# 102711.net
KiCad netlist of a schematic drawn in Altium Designer
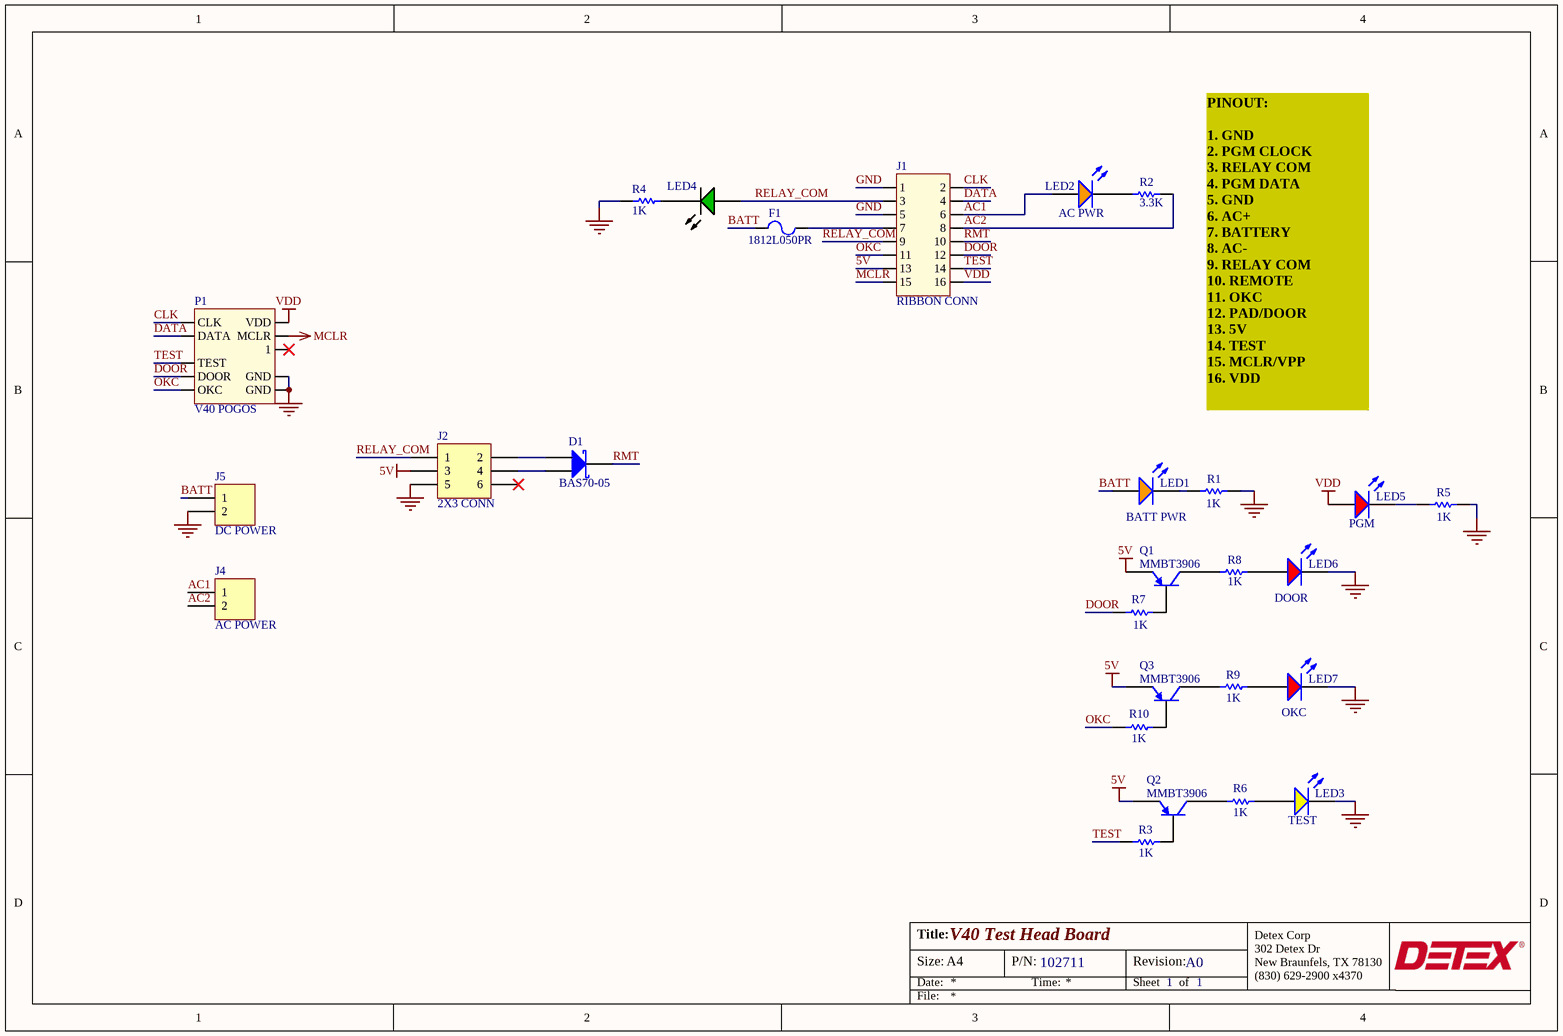
[diagram p0: 102711.SchDoc]

(export (version "E")
  (design (tool "Eeschema 10.0.6"))
  (components
    (comp (ref "D1")
      (value "BAS70-05")
      (footprint "SOT-23_M")
      (description "Dual Schottky Diode")
      (fields (field (name "MFR") "DIODES, INC"))
      (libsource (lib "Miscellaneous Devices") (part "D Schottky"))
    )
    (comp (ref "F1")
      (value "1812L050PR")
      (footprint "LFUS-1812L050_V")
      (fields (field (name "TOLERANCE") "1%"))
      (libsource (lib "Altium Content Vault") (part "CMP-1700-00002-1"))
    )
    (comp (ref "J1")
      (value "2x8 Header")
      (footprint "HDR2X8")
      (fields (field (name "DESC") "RIBBON CONN"))
      (libsource (lib "102709") (part "2x9 Header"))
    )
    (comp (ref "J2")
      (value "2X3 CONN")
      (footprint "HDR2X3")
      (description "Header, 3-Pin, Dual row")
      (fields (field (name "PUBLISHER") "Altium Limited"))
      (libsource (lib "Miscellaneous Connectors") (part "Header 3X2"))
    )
    (comp (ref "J4")
      (value "AC POWER")
      (footprint "HDR1X2")
      (description "Header, 2-Pin")
      (fields (field (name "PUBLISHER") "Altium Limited"))
      (libsource (lib "Miscellaneous Connectors") (part "Header 2"))
    )
    (comp (ref "J5")
      (value "DC POWER")
      (footprint "BAT_CONN")
      (description "Header, 2-Pin")
      (fields (field (name "PUBLISHER") "Altium Limited"))
      (libsource (lib "Miscellaneous Connectors") (part "Header 2"))
    )
    (comp (ref "LED1")
      (value "BATT PWR")
      (footprint "LTST-C170YKT_V")
      (libsource (lib "altium-import") (part "root_0_SYM-0251-00006-1_"))
    )
    (comp (ref "LED2")
      (value "AC PWR")
      (footprint "LTST-C170YKT_V")
      (libsource (lib "altium-import") (part "root_0_SYM-0251-00006-1_"))
    )
    (comp (ref "LED3")
      (value "LTST-C170YKT")
      (footprint "LTST-C170YKT_V")
      (description "LED Uni-Color Yellow, 60 mW, 80 mA, -55 to 85 degC, 2-Pin SMD, RoHS, Tape and Reel")
      (fields (field (name "MANUFACTURER") "Lite-On") (field (name "DESC") "TEST"))
      (libsource (lib "altium-import") (part "root_0_CMP-1674-00003-5_"))
    )
    (comp (ref "LED4")
      (value "LTST-C190GKT")
      (footprint "LTST-C170YKT_V")
      (description "LED Uni-Color Green, 100 mW, 5 V, -55 to 85 degC, 2-Pin SMD, RoHS, Tape and Reel")
      (libsource (lib "altium-import") (part "root_2_CMP-1674-00007-1_"))
    )
    (comp (ref "LED5")
      (value "LTST-C170CKT")
      (footprint "LTST-C170YKT_V")
      (description "LED Uni-Color Red, 100 mW, 200 mA, -55 to 85 degC, 2-Pin SMD, RoHS, Tape and Reel")
      (fields (field (name "MANUFACTURER") "Lite-On") (field (name "DESC") "PGM"))
      (libsource (lib "altium-import") (part "root_0_CMP-1674-00001-5_"))
    )
    (comp (ref "LED6")
      (value "LTST-C170CKT")
      (footprint "LTST-C170YKT_V")
      (description "LED Uni-Color Red, 100 mW, 200 mA, -55 to 85 degC, 2-Pin SMD, RoHS, Tape and Reel")
      (fields (field (name "MANUFACTURER") "Lite-On") (field (name "DESC") "DOOR"))
      (libsource (lib "altium-import") (part "root_0_CMP-1674-00001-5_"))
    )
    (comp (ref "LED7")
      (value "LTST-C170CKT")
      (footprint "LTST-C170YKT_V")
      (description "LED Uni-Color Red, 100 mW, 200 mA, -55 to 85 degC, 2-Pin SMD, RoHS, Tape and Reel")
      (fields (field (name "MANUFACTURER") "Lite-On") (field (name "DESC") "OKC"))
      (libsource (lib "altium-import") (part "root_0_CMP-1674-00001-5_"))
    )
    (comp (ref "P1")
      (value "V40 POGOS")
      (footprint "V40_POGOS")
      (libsource (lib "102711") (part "V40_POGOS"))
    )
    (comp (ref "Q1")
      (value "MMBT3906")
      (footprint "FAIR-SOT23-3_V")
      (description "PNP General-Purpose Amplifier, 40 V, 0.2 A, -55 to 150 degC, 3-Pin SOT23, RoHS, Tape and Reel")
      (fields (field (name "TOLERANCE") "20%"))
      (libsource (lib "Altium Content Vault") (part "CMP-1670-00011-1"))
    )
    (comp (ref "Q2")
      (value "MMBT3906")
      (footprint "FAIR-SOT23-3_V")
      (description "PNP General-Purpose Amplifier, 40 V, 0.2 A, -55 to 150 degC, 3-Pin SOT23, RoHS, Tape and Reel")
      (fields (field (name "TOLERANCE") "20%"))
      (libsource (lib "Altium Content Vault") (part "CMP-1670-00011-1"))
    )
    (comp (ref "Q3")
      (value "MMBT3906")
      (footprint "FAIR-SOT23-3_V")
      (description "PNP General-Purpose Amplifier, 40 V, 0.2 A, -55 to 150 degC, 3-Pin SOT23, RoHS, Tape and Reel")
      (fields (field (name "TOLERANCE") "20%"))
      (libsource (lib "Altium Content Vault") (part "CMP-1670-00011-1"))
    )
    (comp (ref "R1")
      (value "1K")
      (footprint "RESC0805(2012)_M")
      (description "Resistor")
      (fields (field (name "Comment") "Res1") (field (name "PUBLISHER") "Altium Limited"))
      (libsource (lib "Miscellaneous Devices") (part "Res1"))
    )
    (comp (ref "R2")
      (value "3.3K")
      (footprint "RESC0805(2012)_M")
      (description "Resistor")
      (fields (field (name "Comment") "Res1") (field (name "PUBLISHER") "Altium Limited"))
      (libsource (lib "Miscellaneous Devices") (part "Res1"))
    )
    (comp (ref "R3")
      (value "1K")
      (footprint "RESC0805(2012)_M")
      (description "Resistor")
      (fields (field (name "Comment") "Res1") (field (name "PUBLISHER") "Altium Limited"))
      (libsource (lib "Miscellaneous Devices") (part "Res1"))
    )
    (comp (ref "R4")
      (value "1K")
      (footprint "RESC0805(2012)_M")
      (description "Resistor")
      (fields (field (name "Comment") "Res1") (field (name "PUBLISHER") "Altium Limited"))
      (libsource (lib "Miscellaneous Devices") (part "Res1"))
    )
    (comp (ref "R5")
      (value "1K")
      (footprint "RESC0805(2012)_M")
      (description "Resistor")
      (fields (field (name "Comment") "Res1") (field (name "PUBLISHER") "Altium Limited"))
      (libsource (lib "Miscellaneous Devices") (part "Res1"))
    )
    (comp (ref "R6")
      (value "1K")
      (footprint "RESC0805(2012)_M")
      (description "Resistor")
      (fields (field (name "Comment") "Res1") (field (name "PUBLISHER") "Altium Limited"))
      (libsource (lib "Miscellaneous Devices") (part "Res1"))
    )
    (comp (ref "R7")
      (value "1K")
      (footprint "RESC0805(2012)_M")
      (description "Resistor")
      (fields (field (name "Comment") "Res1") (field (name "PUBLISHER") "Altium Limited"))
      (libsource (lib "Miscellaneous Devices") (part "Res1"))
    )
    (comp (ref "R8")
      (value "1K")
      (footprint "RESC0805(2012)_M")
      (description "Resistor")
      (fields (field (name "Comment") "Res1") (field (name "PUBLISHER") "Altium Limited"))
      (libsource (lib "Miscellaneous Devices") (part "Res1"))
    )
    (comp (ref "R9")
      (value "1K")
      (footprint "RESC0805(2012)_M")
      (description "Resistor")
      (fields (field (name "Comment") "Res1") (field (name "PUBLISHER") "Altium Limited"))
      (libsource (lib "Miscellaneous Devices") (part "Res1"))
    )
    (comp (ref "R10")
      (value "1K")
      (footprint "RESC0805(2012)_M")
      (description "Resistor")
      (fields (field (name "Comment") "Res1") (field (name "PUBLISHER") "Altium Limited"))
      (libsource (lib "Miscellaneous Devices") (part "Res1"))
    )
  )
  (nets
    (net (code "1") (name "/AC1") (class "Default")
      (node (ref "J1") (pin "6") (pinfunction "6_6") (pintype "passive"))
      (node (ref "J4") (pin "1") (pinfunction "1_1") (pintype "passive"))
      (node (ref "LED2") (pin "1") (pinfunction "A_1") (pintype "passive"))
    )
    (net (code "2") (name "/AC2") (class "Default")
      (node (ref "J1") (pin "8") (pinfunction "8_8") (pintype "passive"))
      (node (ref "J4") (pin "2") (pinfunction "2_2") (pintype "passive"))
      (node (ref "R2") (pin "2") (pinfunction "2_2") (pintype "passive"))
    )
    (net (code "3") (name "/BATT") (class "Default")
      (node (ref "F1") (pin "1") (pinfunction "1_1") (pintype "passive"))
      (node (ref "J5") (pin "1") (pinfunction "1_1") (pintype "passive"))
      (node (ref "LED1") (pin "1") (pinfunction "A_1") (pintype "passive"))
    )
    (net (code "4") (name "/CLK") (class "Default")
      (node (ref "J1") (pin "2") (pinfunction "2_2") (pintype "passive"))
      (node (ref "P1") (pin "3") (pinfunction "CLK_3") (pintype "passive"))
    )
    (net (code "5") (name "/DATA") (class "Default")
      (node (ref "J1") (pin "4") (pinfunction "4_4") (pintype "passive"))
      (node (ref "P1") (pin "4") (pinfunction "DATA_4") (pintype "passive"))
    )
    (net (code "6") (name "/DOOR") (class "Default")
      (node (ref "J1") (pin "12") (pinfunction "12_12") (pintype "passive"))
      (node (ref "P1") (pin "9") (pinfunction "DOOR_9") (pintype "passive"))
      (node (ref "R7") (pin "1") (pinfunction "1_1") (pintype "passive"))
    )
    (net (code "7") (name "/OKC") (class "Default")
      (node (ref "J1") (pin "11") (pinfunction "11_11") (pintype "passive"))
      (node (ref "P1") (pin "10") (pinfunction "OKC_10") (pintype "passive"))
      (node (ref "R10") (pin "1") (pinfunction "1_1") (pintype "passive"))
    )
    (net (code "8") (name "/RELAY_COM") (class "Default")
      (node (ref "J1") (pin "3") (pinfunction "3_3") (pintype "passive"))
      (node (ref "J1") (pin "9") (pinfunction "9_9") (pintype "passive"))
      (node (ref "J2") (pin "1") (pinfunction "1_1") (pintype "passive"))
      (node (ref "LED4") (pin "1") (pinfunction "A_1") (pintype "passive"))
    )
    (net (code "9") (name "/RMT") (class "Default")
      (node (ref "D1") (pin "3") (pinfunction "K_3") (pintype "passive"))
      (node (ref "J1") (pin "10") (pinfunction "10_10") (pintype "passive"))
    )
    (net (code "10") (name "/TEST") (class "Default")
      (node (ref "J1") (pin "14") (pinfunction "14_14") (pintype "passive"))
      (node (ref "P1") (pin "7") (pinfunction "TEST_7") (pintype "passive"))
      (node (ref "R3") (pin "1") (pinfunction "1_1") (pintype "passive"))
    )
    (net (code "11") (name "5V") (class "Default")
      (node (ref "J1") (pin "13") (pinfunction "13_13") (pintype "passive"))
      (node (ref "J2") (pin "3") (pinfunction "3_3") (pintype "passive"))
      (node (ref "Q1") (pin "2") (pinfunction "E_2") (pintype "passive"))
      (node (ref "Q2") (pin "2") (pinfunction "E_2") (pintype "passive"))
      (node (ref "Q3") (pin "2") (pinfunction "E_2") (pintype "passive"))
    )
    (net (code "12") (name "GND") (class "Default")
      (node (ref "J1") (pin "1") (pinfunction "1_1") (pintype "passive"))
      (node (ref "J1") (pin "5") (pinfunction "5_5") (pintype "passive"))
      (node (ref "J2") (pin "5") (pinfunction "5_5") (pintype "passive"))
      (node (ref "J5") (pin "2") (pinfunction "2_2") (pintype "passive"))
      (node (ref "LED3") (pin "2") (pinfunction "K_2") (pintype "passive"))
      (node (ref "LED6") (pin "2") (pinfunction "K_2") (pintype "passive"))
      (node (ref "LED7") (pin "2") (pinfunction "K_2") (pintype "passive"))
      (node (ref "P1") (pin "2") (pinfunction "GND_2") (pintype "passive"))
      (node (ref "P1") (pin "8") (pinfunction "GND_8") (pintype "passive"))
      (node (ref "R1") (pin "2") (pinfunction "2_2") (pintype "passive"))
      (node (ref "R4") (pin "2") (pinfunction "2_2") (pintype "passive"))
      (node (ref "R5") (pin "2") (pinfunction "2_2") (pintype "passive"))
    )
    (net (code "13") (name "MCLR") (class "Default")
      (node (ref "J1") (pin "15") (pinfunction "15_15") (pintype "passive"))
      (node (ref "P1") (pin "5") (pinfunction "MCLR_5") (pintype "passive"))
    )
    (net (code "14") (name "Net-(D1-A-Pad1)") (class "Default")
      (node (ref "D1") (pin "1") (pinfunction "A_1") (pintype "passive"))
      (node (ref "J2") (pin "4") (pinfunction "4_4") (pintype "passive"))
    )
    (net (code "15") (name "Net-(D1-A-Pad2)") (class "Default")
      (node (ref "D1") (pin "2") (pinfunction "A_2") (pintype "passive"))
      (node (ref "J2") (pin "2") (pinfunction "2_2") (pintype "passive"))
    )
    (net (code "16") (name "Net-(F1-Pad2)") (class "Default")
      (node (ref "F1") (pin "2") (pinfunction "2_2") (pintype "passive"))
      (node (ref "J1") (pin "7") (pinfunction "7_7") (pintype "passive"))
    )
    (net (code "17") (name "Net-(LED1-K)") (class "Default")
      (node (ref "LED1") (pin "2") (pinfunction "K_2") (pintype "passive"))
      (node (ref "R1") (pin "1") (pinfunction "1_1") (pintype "passive"))
    )
    (net (code "18") (name "Net-(LED2-K)") (class "Default")
      (node (ref "LED2") (pin "2") (pinfunction "K_2") (pintype "passive"))
      (node (ref "R2") (pin "1") (pinfunction "1_1") (pintype "passive"))
    )
    (net (code "19") (name "Net-(LED3-A)") (class "Default")
      (node (ref "LED3") (pin "1") (pinfunction "A_1") (pintype "passive"))
      (node (ref "R6") (pin "2") (pinfunction "2_2") (pintype "passive"))
    )
    (net (code "20") (name "Net-(LED4-K)") (class "Default")
      (node (ref "LED4") (pin "2") (pinfunction "K_2") (pintype "passive"))
      (node (ref "R4") (pin "1") (pinfunction "1_1") (pintype "passive"))
    )
    (net (code "21") (name "Net-(LED5-K)") (class "Default")
      (node (ref "LED5") (pin "2") (pinfunction "K_2") (pintype "passive"))
      (node (ref "R5") (pin "1") (pinfunction "1_1") (pintype "passive"))
    )
    (net (code "22") (name "Net-(LED6-A)") (class "Default")
      (node (ref "LED6") (pin "1") (pinfunction "A_1") (pintype "passive"))
      (node (ref "R8") (pin "2") (pinfunction "2_2") (pintype "passive"))
    )
    (net (code "23") (name "Net-(LED7-A)") (class "Default")
      (node (ref "LED7") (pin "1") (pinfunction "A_1") (pintype "passive"))
      (node (ref "R9") (pin "2") (pinfunction "2_2") (pintype "passive"))
    )
    (net (code "24") (name "Net-(Q1-B)") (class "Default")
      (node (ref "Q1") (pin "1") (pinfunction "B_1") (pintype "passive"))
      (node (ref "R7") (pin "2") (pinfunction "2_2") (pintype "passive"))
    )
    (net (code "25") (name "Net-(Q1-C)") (class "Default")
      (node (ref "Q1") (pin "3") (pinfunction "C_3") (pintype "passive"))
      (node (ref "R8") (pin "1") (pinfunction "1_1") (pintype "passive"))
    )
    (net (code "26") (name "Net-(Q2-B)") (class "Default")
      (node (ref "Q2") (pin "1") (pinfunction "B_1") (pintype "passive"))
      (node (ref "R3") (pin "2") (pinfunction "2_2") (pintype "passive"))
    )
    (net (code "27") (name "Net-(Q2-C)") (class "Default")
      (node (ref "Q2") (pin "3") (pinfunction "C_3") (pintype "passive"))
      (node (ref "R6") (pin "1") (pinfunction "1_1") (pintype "passive"))
    )
    (net (code "28") (name "Net-(Q3-B)") (class "Default")
      (node (ref "Q3") (pin "1") (pinfunction "B_1") (pintype "passive"))
      (node (ref "R10") (pin "2") (pinfunction "2_2") (pintype "passive"))
    )
    (net (code "29") (name "Net-(Q3-C)") (class "Default")
      (node (ref "Q3") (pin "3") (pinfunction "C_3") (pintype "passive"))
      (node (ref "R9") (pin "1") (pinfunction "1_1") (pintype "passive"))
    )
    (net (code "30") (name "VDD") (class "Default")
      (node (ref "J1") (pin "16") (pinfunction "16_16") (pintype "passive"))
      (node (ref "LED5") (pin "1") (pinfunction "A_1") (pintype "passive"))
      (node (ref "P1") (pin "6") (pinfunction "VDD_6") (pintype "passive"))
    )
    (net (code "31") (name "unconnected-(J2-Pad6)") (class "Default")
      (node (ref "J2") (pin "6") (pinfunction "6_6") (pintype "passive+no_connect"))
    )
    (net (code "32") (name "unconnected-(P1-Pad1)") (class "Default")
      (node (ref "P1") (pin "1") (pinfunction "1_1") (pintype "passive+no_connect"))
    )
  )
)
